# TW3-16_V0_2.net
KiCad netlist of a schematic drawn in Altium Designer
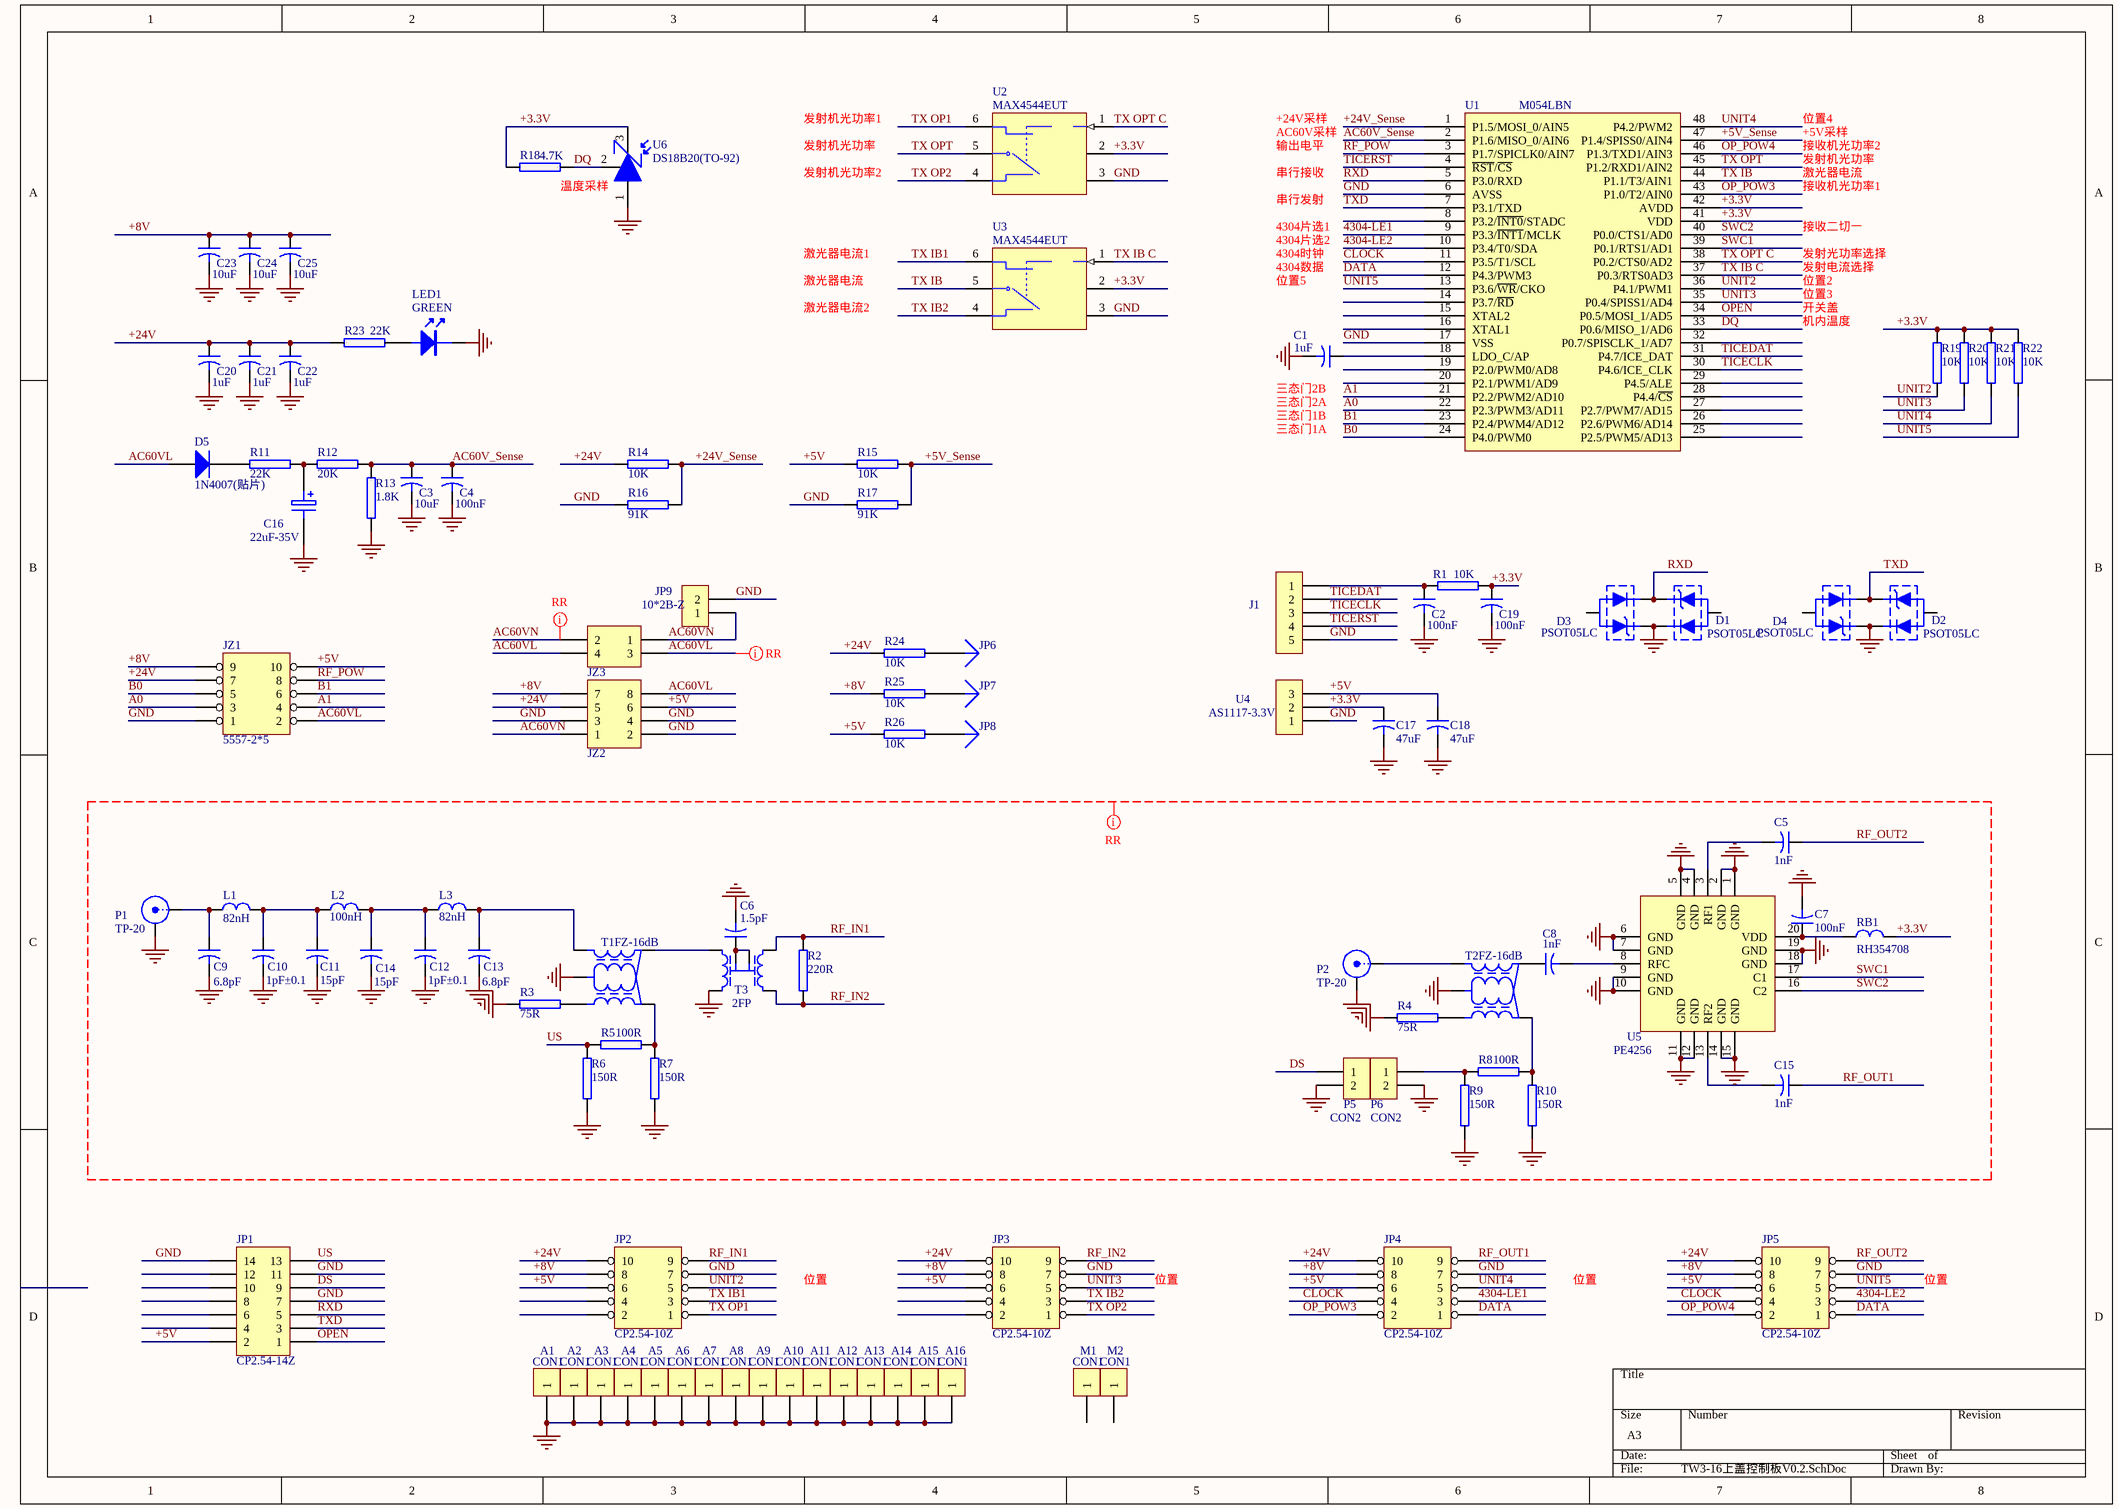
[diagram p0: TW3-16上盖控制板V0.2.SchDoc]

(export (version "E")
  (design (tool "Eeschema 10.0.6"))
  (components
    (comp (ref "A1")
      (value "CON1")
      (footprint "PAD-6mm")
      (description "Connector")
      (libsource (lib "Miscellaneous Devices") (part "CON1"))
    )
    (comp (ref "A2")
      (value "CON1")
      (footprint "PAD-6mm")
      (description "Connector")
      (libsource (lib "Miscellaneous Devices") (part "CON1"))
    )
    (comp (ref "A3")
      (value "CON1")
      (footprint "PAD-6mm")
      (description "Connector")
      (libsource (lib "Miscellaneous Devices") (part "CON1"))
    )
    (comp (ref "A4")
      (value "CON1")
      (footprint "PAD-6mm")
      (description "Connector")
      (libsource (lib "Miscellaneous Devices") (part "CON1"))
    )
    (comp (ref "A5")
      (value "CON1")
      (footprint "PAD-6mm")
      (description "Connector")
      (libsource (lib "Miscellaneous Devices") (part "CON1"))
    )
    (comp (ref "A6")
      (value "CON1")
      (footprint "PAD-6mm")
      (description "Connector")
      (libsource (lib "Miscellaneous Devices") (part "CON1"))
    )
    (comp (ref "A7")
      (value "CON1")
      (footprint "PAD-6mm")
      (description "Connector")
      (libsource (lib "Miscellaneous Devices") (part "CON1"))
    )
    (comp (ref "A8")
      (value "CON1")
      (footprint "PAD-6mm")
      (description "Connector")
      (libsource (lib "Miscellaneous Devices") (part "CON1"))
    )
    (comp (ref "A9")
      (value "CON1")
      (footprint "PAD-6mm")
      (description "Connector")
      (libsource (lib "Miscellaneous Devices") (part "CON1"))
    )
    (comp (ref "A10")
      (value "CON1")
      (footprint "PAD-6mm")
      (description "Connector")
      (libsource (lib "Miscellaneous Devices") (part "CON1"))
    )
    (comp (ref "A11")
      (value "CON1")
      (footprint "PAD-6mm")
      (description "Connector")
      (libsource (lib "Miscellaneous Devices") (part "CON1"))
    )
    (comp (ref "A12")
      (value "CON1")
      (footprint "PAD-6mm")
      (description "Connector")
      (libsource (lib "Miscellaneous Devices") (part "CON1"))
    )
    (comp (ref "A13")
      (value "CON1")
      (footprint "PAD-6mm")
      (description "Connector")
      (libsource (lib "Miscellaneous Devices") (part "CON1"))
    )
    (comp (ref "A14")
      (value "CON1")
      (footprint "PAD-6mm")
      (description "Connector")
      (libsource (lib "Miscellaneous Devices") (part "CON1"))
    )
    (comp (ref "A15")
      (value "CON1")
      (footprint "PAD-6mm")
      (description "Connector")
      (libsource (lib "Miscellaneous Devices") (part "CON1"))
    )
    (comp (ref "A16")
      (value "CON1")
      (footprint "PAD-6mm")
      (description "Connector")
      (libsource (lib "Miscellaneous Devices") (part "CON1"))
    )
    (comp (ref "C1")
      (value "1uF")
      (footprint "0603")
      (description "贴片电容")
      (fields (field (name "Comment") "CT41-0603-B1uF-25V-K"))
      (libsource (lib "Miscellaneous Devices") (part "Cap2"))
    )
    (comp (ref "C2")
      (value "100nF")
      (footprint "0603")
      (description "贴片电容")
      (fields (field (name "Comment") "CT41-0603-B100nF-50V-K"))
      (libsource (lib "Miscellaneous Devices") (part "Cap2"))
    )
    (comp (ref "C3")
      (value "10uF")
      (footprint "1206")
      (description "贴片电容")
      (fields (field (name "Comment") "16V-10uF±10%-X7R-1206"))
      (libsource (lib "Miscellaneous Devices") (part "Cap2"))
    )
    (comp (ref "C4")
      (value "100nF")
      (footprint "0603")
      (description "贴片电容")
      (fields (field (name "Comment") "CT41-0603-B100nF-50V-K"))
      (libsource (lib "Miscellaneous Devices") (part "Cap2"))
    )
    (comp (ref "C5")
      (value "1nF")
      (footprint "0603")
      (description "贴片电容")
      (fields (field (name "Comment") "CT41-0603-B1nF-50V-J"))
      (libsource (lib "Miscellaneous Devices") (part "Cap2"))
    )
    (comp (ref "C6")
      (value "1.5pF")
      (footprint "0603")
      (description "贴片电容")
      (fields (field (name "Comment") "CC41-0603-CG1.5pF-50V-C"))
      (libsource (lib "Miscellaneous Devices") (part "Cap2"))
    )
    (comp (ref "C7")
      (value "100nF")
      (footprint "0603")
      (description "贴片电容")
      (fields (field (name "Comment") "CT41-0603-B100nF-50V-K"))
      (libsource (lib "Miscellaneous Devices") (part "Cap2"))
    )
    (comp (ref "C8")
      (value "1nF")
      (footprint "0603")
      (description "贴片电容")
      (fields (field (name "Comment") "CT41-0603-B1nF-50V-J"))
      (libsource (lib "Miscellaneous Devices") (part "Cap2"))
    )
    (comp (ref "C9")
      (value "6.8pF")
      (footprint "0603")
      (description "贴片电容")
      (fields (field (name "Comment") "CC41-0603-CG6.8pF-50V-C"))
      (libsource (lib "Miscellaneous Devices") (part "Cap2"))
    )
    (comp (ref "C10")
      (value "1pF±0.1")
      (footprint "0603")
      (description "贴片电容")
      (fields (field (name "Comment") "CC41-0603-CG1pF-50V-B"))
      (libsource (lib "Miscellaneous Devices") (part "Cap2"))
    )
    (comp (ref "C11")
      (value "15pF")
      (footprint "0603")
      (description "贴片电容")
      (fields (field (name "Comment") "CC41-0603-CG15pF-50V-J"))
      (libsource (lib "Miscellaneous Devices") (part "Cap2"))
    )
    (comp (ref "C12")
      (value "1pF±0.1")
      (footprint "0603")
      (description "贴片电容")
      (fields (field (name "Comment") "CC41-0603-CG1pF-50V-B"))
      (libsource (lib "Miscellaneous Devices") (part "Cap2"))
    )
    (comp (ref "C13")
      (value "6.8pF")
      (footprint "0603")
      (description "贴片电容")
      (fields (field (name "Comment") "CC41-0603-CG6.8pF-50V-C"))
      (libsource (lib "Miscellaneous Devices") (part "Cap2"))
    )
    (comp (ref "C14")
      (value "15pF")
      (footprint "0603")
      (description "贴片电容")
      (fields (field (name "Comment") "CC41-0603-CG15pF-50V-J"))
      (libsource (lib "Miscellaneous Devices") (part "Cap2"))
    )
    (comp (ref "C15")
      (value "1nF")
      (footprint "0603")
      (description "贴片电容")
      (fields (field (name "Comment") "CT41-0603-B1nF-50V-J"))
      (libsource (lib "Miscellaneous Devices") (part "Cap2"))
    )
    (comp (ref "C16")
      (value "22uF-35V")
      (footprint "RB-SMT-6.3X5.4")
      (description "贴片铝电解电容")
      (fields (field (name "Comment") "SCD11-6.3*5.4-22uF-35V-K"))
      (libsource (lib "Miscellaneous Devices") (part "ELECTRO1"))
    )
    (comp (ref "C17")
      (value "47uF")
      (footprint "1206")
      (description "贴片电容")
      (fields (field (name "Comment") "CT41-1206-F476-10V-M"))
      (libsource (lib "Miscellaneous Devices") (part "Cap2"))
    )
    (comp (ref "C18")
      (value "47uF")
      (footprint "1206")
      (description "贴片电容")
      (fields (field (name "Comment") "CT41-1206-F476-10V-M"))
      (libsource (lib "Miscellaneous Devices") (part "Cap2"))
    )
    (comp (ref "C19")
      (value "100nF")
      (footprint "0603")
      (description "贴片电容")
      (fields (field (name "Comment") "CT41-0603-B100nF-50V-K"))
      (libsource (lib "Miscellaneous Devices") (part "Cap2"))
    )
    (comp (ref "C20")
      (value "1uF")
      (footprint "1206")
      (description "贴片电容")
      (fields (field (name "Comment") "CT41-1206-B1uF-50V-K"))
      (libsource (lib "Miscellaneous Devices") (part "Cap2"))
    )
    (comp (ref "C21")
      (value "1uF")
      (footprint "1206")
      (description "贴片电容")
      (fields (field (name "Comment") "CT41-1206-B1uF-50V-K"))
      (libsource (lib "Miscellaneous Devices") (part "Cap2"))
    )
    (comp (ref "C22")
      (value "1uF")
      (footprint "1206")
      (description "贴片电容")
      (fields (field (name "Comment") "CT41-1206-B1uF-50V-K"))
      (libsource (lib "Miscellaneous Devices") (part "Cap2"))
    )
    (comp (ref "C23")
      (value "10uF")
      (footprint "1206")
      (description "贴片电容")
      (fields (field (name "Comment") "16V-10uF±10%-X7R-1206"))
      (libsource (lib "Miscellaneous Devices") (part "Cap2"))
    )
    (comp (ref "C24")
      (value "10uF")
      (footprint "1206")
      (description "贴片电容")
      (fields (field (name "Comment") "16V-10uF±10%-X7R-1206"))
      (libsource (lib "Miscellaneous Devices") (part "Cap2"))
    )
    (comp (ref "C25")
      (value "10uF")
      (footprint "1206")
      (description "贴片电容")
      (fields (field (name "Comment") "16V-10uF±10%-X7R-1206"))
      (libsource (lib "Miscellaneous Devices") (part "Cap2"))
    )
    (comp (ref "D1")
      (value "PSOT05LC")
      (footprint "SOT-23")
      (fields (field (name "Comment") "集成块"))
      (libsource (lib "*") (part "PSOT05LC"))
    )
    (comp (ref "D2")
      (value "PSOT05LC")
      (footprint "SOT-23")
      (fields (field (name "Comment") "集成块"))
      (libsource (lib "*") (part "PSOT05LC"))
    )
    (comp (ref "D3")
      (value "PSOT05LC")
      (footprint "SOT-23")
      (fields (field (name "Comment") "集成块"))
      (libsource (lib "*") (part "PSOT05LC"))
    )
    (comp (ref "D4")
      (value "PSOT05LC")
      (footprint "SOT-23")
      (fields (field (name "Comment") "集成块"))
      (libsource (lib "*") (part "PSOT05LC"))
    )
    (comp (ref "D5")
      (value "1N4007(贴片)")
      (footprint "DO-SMA")
      (description "贴片二极管")
      (libsource (lib "Miscellaneous Devices") (part "Diode 1N4007"))
    )
    (comp (ref "J1")
      (value "IDC单排插针")
      (footprint "SIP5")
      (description "1×5（2.54mm）")
      (libsource (lib "*") (part "CON5"))
    )
    (comp (ref "JP1")
      (value "CP2.54-14Z-S-K(排母)")
      (footprint "IDC-14Z")
      (description "双排14芯插座")
      (fields (field (name "VALLUE") "CP2.54-14Z"))
      (libsource (lib "Miscellaneous Connectors") (part "Header 7X2"))
    )
    (comp (ref "JP2")
      (value "CP2.54-10Z")
      (footprint "IDC-10Z")
      (description "双排10芯插座")
      (fields (field (name "Comment") "CP2.54-10Z-S-K(排母)"))
      (libsource (lib "Miscellaneous Devices") (part "HEADER 5X2"))
    )
    (comp (ref "JP3")
      (value "CP2.54-10Z")
      (footprint "IDC-10Z")
      (description "双排10芯插座")
      (fields (field (name "Comment") "CP2.54-10Z-S-K(排母)"))
      (libsource (lib "Miscellaneous Devices") (part "HEADER 5X2"))
    )
    (comp (ref "JP4")
      (value "CP2.54-10Z")
      (footprint "IDC-10Z")
      (description "双排10芯插座")
      (fields (field (name "Comment") "CP2.54-10Z-S-K(排母)"))
      (libsource (lib "Miscellaneous Devices") (part "HEADER 5X2"))
    )
    (comp (ref "JP5")
      (value "CP2.54-10Z")
      (footprint "IDC-10Z")
      (description "双排10芯插座")
      (fields (field (name "Comment") "CP2.54-10Z-S-K(排母)"))
      (libsource (lib "Miscellaneous Devices") (part "HEADER 5X2"))
    )
    (comp (ref "JP6")
      (value "CK-1A")
      (footprint "TEST1")
      (description "测试柱")
      (libsource (lib "Miscellaneous Connectors") (part "Plug"))
    )
    (comp (ref "JP7")
      (value "CK-1A")
      (footprint "TEST1")
      (description "测试柱")
      (libsource (lib "Miscellaneous Connectors") (part "Plug"))
    )
    (comp (ref "JP8")
      (value "CK-1A")
      (footprint "TEST1")
      (description "测试柱")
      (libsource (lib "Miscellaneous Connectors") (part "Plug"))
    )
    (comp (ref "JP9")
      (value "10*2B-Z")
      (footprint "AC-10mm")
      (description "二芯针座")
      (libsource (lib "") (part "CON2_1"))
    )
    (comp (ref "JZ1")
      (value "5557-2*5")
      (footprint "5557-2*5")
      (description "十芯插座")
      (libsource (lib "") (part "HEADER 5X2_1"))
    )
    (comp (ref "JZ2")
      (value "5557-8A")
      (footprint "5557-2X4")
      (description "八芯插座")
      (libsource (lib "Miscellaneous Connectors") (part "Header 4X2H"))
    )
    (comp (ref "JZ3")
      (value "5557-2*2座")
      (footprint "5557-2X2")
      (description "4芯插座")
      (libsource (lib "Miscellaneous Connectors") (part "Header 2X2H"))
    )
    (comp (ref "L1")
      (value "82nH")
      (footprint "0805")
      (description "陶瓷线绕电感")
      (fields (field (name "Comment") "HDW0805UC082JGT"))
      (libsource (lib "SCH") (part "L3"))
    )
    (comp (ref "L2")
      (value "100nH")
      (footprint "0805")
      (description "陶瓷线绕电感")
      (fields (field (name "Comment") "HDW0805UCR10JGT"))
      (libsource (lib "SCH") (part "L3"))
    )
    (comp (ref "L3")
      (value "82nH")
      (footprint "0805")
      (description "陶瓷线绕电感")
      (fields (field (name "Comment") "HDW1008UC082JGT"))
      (libsource (lib "SCH") (part "L3"))
    )
    (comp (ref "LED1")
      (value "GREEN")
      (footprint "1206-D")
      (description "发光二极管")
      (fields (field (name "Comment") "LED-1206-G(SMD)"))
      (libsource (lib "SCH") (part "LED-1"))
    )
    (comp (ref "M1")
      (value "CON1")
      (footprint "MArK-1")
      (description "Connector")
      (libsource (lib "Miscellaneous Devices") (part "CON1"))
    )
    (comp (ref "M2")
      (value "CON1")
      (footprint "MArK-1")
      (description "Connector")
      (libsource (lib "Miscellaneous Devices") (part "CON1"))
    )
    (comp (ref "P1")
      (value "TP-20")
      (footprint "PAD-DLJT2")
      (description "测试插孔")
      (fields (field (name "Comment") "02TV阳座"))
      (libsource (lib "Miscellaneous Connectors") (part "SMB"))
    )
    (comp (ref "P2")
      (value "TP-20")
      (footprint "PAD-DLJT2")
      (description "测试插孔")
      (fields (field (name "Comment") "02TV阳座"))
      (libsource (lib "Miscellaneous Connectors") (part "SMB"))
    )
    (comp (ref "P5")
      (value "CON2")
      (footprint "PAD-DLJT2")
      (description "Connector")
      (libsource (lib "") (part "CON2_2"))
    )
    (comp (ref "P6")
      (value "CON2")
      (footprint "PAD-DLJT2")
      (description "Connector")
      (libsource (lib "Miscellaneous Devices") (part "CON2"))
    )
    (comp (ref "R1")
      (value "10K")
      (footprint "0603")
      (description "贴片电阻")
      (fields (field (name "Comment") "SRI11-0603-10KΩ-J"))
      (libsource (lib "") (part "RES1_3"))
    )
    (comp (ref "R2")
      (value "220R")
      (footprint "0603")
      (description "贴片电阻")
      (fields (field (name "Comment") "SRI11-0603-220Ω-J"))
      (libsource (lib "*") (part "RES1"))
    )
    (comp (ref "R3")
      (value "75R")
      (footprint "0603")
      (description "贴片电阻")
      (fields (field (name "Comment") "SRI11-0603-75Ω-J"))
      (libsource (lib "") (part "RES1_1"))
    )
    (comp (ref "R4")
      (value "75R")
      (footprint "0603")
      (description "贴片电阻")
      (fields (field (name "Comment") "SRI11-0603-75Ω-J"))
      (libsource (lib "") (part "RES1_1"))
    )
    (comp (ref "R5")
      (value "100R")
      (footprint "0603")
      (description "贴片电阻")
      (fields (field (name "Comment") "SRI11-0603-100Ω-J"))
      (libsource (lib "") (part "RES1_1"))
    )
    (comp (ref "R6")
      (value "150R")
      (footprint "0603")
      (description "贴片电阻")
      (fields (field (name "Comment") "SRI11-0603-150Ω-J"))
      (libsource (lib "") (part "RES1_2"))
    )
    (comp (ref "R7")
      (value "150R")
      (footprint "0603")
      (description "贴片电阻")
      (fields (field (name "Comment") "SRI11-0603-150Ω-J"))
      (libsource (lib "") (part "RES1_2"))
    )
    (comp (ref "R8")
      (value "100R")
      (footprint "0603")
      (description "贴片电阻")
      (fields (field (name "Comment") "SRI11-0603-100Ω-J"))
      (libsource (lib "") (part "RES1_1"))
    )
    (comp (ref "R9")
      (value "150R")
      (footprint "0603")
      (description "贴片电阻")
      (fields (field (name "Comment") "SRI11-0603-150Ω-J"))
      (libsource (lib "") (part "RES1_2"))
    )
    (comp (ref "R10")
      (value "150R")
      (footprint "0603")
      (description "贴片电阻")
      (fields (field (name "Comment") "SRI11-0603-150Ω-J"))
      (libsource (lib "") (part "RES1_2"))
    )
    (comp (ref "R11")
      (value "22K")
      (footprint "0805")
      (description "贴片电阻")
      (fields (field (name "Comment") "SRI11-0805-22KΩ-J"))
      (libsource (lib "*") (part "RES1"))
    )
    (comp (ref "R12")
      (value "20K")
      (footprint "0805")
      (description "贴片电阻")
      (fields (field (name "Comment") "SRI11-0805-20KΩ-J"))
      (libsource (lib "*") (part "RES1"))
    )
    (comp (ref "R13")
      (value "1.8K")
      (footprint "0805")
      (description "贴片电阻")
      (fields (field (name "Comment") "SRI11-0805-1.8KΩ-J"))
      (libsource (lib "") (part "RES1_4"))
    )
    (comp (ref "R14")
      (value "10K")
      (footprint "0603")
      (description "贴片电阻")
      (fields (field (name "Comment") "SRI11-0603-10KΩ-J"))
      (libsource (lib "") (part "RES1_1"))
    )
    (comp (ref "R15")
      (value "10K")
      (footprint "0603")
      (description "贴片电阻")
      (fields (field (name "Comment") "SRI11-0603-10KΩ-J"))
      (libsource (lib "") (part "RES1_1"))
    )
    (comp (ref "R16")
      (value "91K")
      (footprint "0603")
      (description "贴片电阻")
      (fields (field (name "Comment") "SRI11-0603-91KΩ-J"))
      (libsource (lib "") (part "RES1_1"))
    )
    (comp (ref "R17")
      (value "91K")
      (footprint "0603")
      (description "贴片电阻")
      (fields (field (name "Comment") "SRI11-0603-91KΩ-J"))
      (libsource (lib "") (part "RES1_1"))
    )
    (comp (ref "R18")
      (value "4.7K")
      (footprint "0603")
      (description "贴片电阻")
      (fields (field (name "Comment") "SRI11-0603-4.7KΩ-J"))
      (libsource (lib "") (part "RES1_2"))
    )
    (comp (ref "R19")
      (value "10K")
      (footprint "0603")
      (description "贴片电阻")
      (fields (field (name "Comment") "SRI11-0603-10KΩ-J"))
      (libsource (lib "") (part "RES1_1"))
    )
    (comp (ref "R20")
      (value "10K")
      (footprint "0603")
      (description "贴片电阻")
      (fields (field (name "Comment") "SRI11-0603-10KΩ-J"))
      (libsource (lib "") (part "RES1_1"))
    )
    (comp (ref "R21")
      (value "10K")
      (footprint "0603")
      (description "贴片电阻")
      (fields (field (name "Comment") "SRI11-0603-10KΩ-J"))
      (libsource (lib "") (part "RES1_1"))
    )
    (comp (ref "R22")
      (value "10K")
      (footprint "0603")
      (description "贴片电阻")
      (fields (field (name "Comment") "SRI11-0603-10KΩ-J"))
      (libsource (lib "") (part "RES1_1"))
    )
    (comp (ref "R23")
      (value "22K")
      (footprint "0603")
      (description "贴片电阻")
      (fields (field (name "Comment") "SRI11-0603-22KΩ-J"))
      (libsource (lib "*") (part "RESSMD_0603"))
    )
    (comp (ref "R24")
      (value "10K")
      (footprint "0603")
      (description "贴片电阻")
      (fields (field (name "Comment") "SRI11-0603-10KΩ-J"))
      (libsource (lib "") (part "RES1_1"))
    )
    (comp (ref "R25")
      (value "10K")
      (footprint "0603")
      (description "贴片电阻")
      (fields (field (name "Comment") "SRI11-0603-10KΩ-J"))
      (libsource (lib "") (part "RES1_1"))
    )
    (comp (ref "R26")
      (value "10K")
      (footprint "0603")
      (description "贴片电阻")
      (fields (field (name "Comment") "SRI11-0603-10KΩ-J"))
      (libsource (lib "") (part "RES1_1"))
    )
    (comp (ref "RB1")
      (value "RH354708")
      (footprint "L12MM")
      (description "插件磁珠")
      (libsource (lib "SCH") (part "L3"))
    )
    (comp (ref "T1")
      (value "FZ-16dB")
      (footprint "T-SM16")
      (description "高频变压器")
      (fields (field (name "Comment") "F06401C"))
      (libsource (lib "SCH") (part "FZ"))
    )
    (comp (ref "T2")
      (value "FZ-16dB")
      (footprint "T-SM16")
      (description "高频变压器")
      (fields (field (name "Comment") "F06401C"))
      (libsource (lib "SCH") (part "FZ"))
    )
    (comp (ref "T3")
      (value "2FP")
      (footprint "STB-RG33")
      (description "高频变压器")
      (fields (field (name "Comment") "F06502S"))
      (libsource (lib "*") (part "FP"))
    )
    (comp (ref "U1")
      (value "M054LBN")
      (footprint "LQFP-48")
      (description "集成块")
      (libsource (lib "*") (part "M052LBN"))
    )
    (comp (ref "U2")
      (value "MAX4544EUT")
      (footprint "SOT23-6")
      (fields (field (name "Comment") "集成块"))
      (libsource (lib "*") (part "MAX4544EUT-T"))
    )
    (comp (ref "U3")
      (value "MAX4544EUT")
      (footprint "SOT23-6")
      (fields (field (name "Comment") "集成块"))
      (libsource (lib "*") (part "MAX4544EUT-T"))
    )
    (comp (ref "U4")
      (value "AS1117-3.3V")
      (footprint "SOT-223-3L")
      (description "集成块")
      (libsource (lib "Miscellaneous Devices") (part "CON3"))
    )
    (comp (ref "U5")
      (value "PE4256")
      (footprint "QFN-20")
      (description "集成块")
      (fields (field (name "Comment") "PE4256DS"))
      (libsource (lib "*") (part "PE4256"))
    )
    (comp (ref "U6")
      (value "DS18B20(TO-92)")
      (footprint "TO-92-78L")
      (description "集成块")
      (libsource (lib "*") (part "DS18B20"))
    )
  )
  (nets
    (net (code "1") (name "/+3.3V") (class "Default")
      (node (ref "C17") (pin "1") (pinfunction "1_1") (pintype "passive"))
      (node (ref "C19") (pin "1") (pinfunction "1_1") (pintype "passive"))
      (node (ref "R1") (pin "2") (pinfunction "2_2") (pintype "passive"))
      (node (ref "R18") (pin "2") (pinfunction "2_2") (pintype "passive"))
      (node (ref "R19") (pin "1") (pinfunction "1_1") (pintype "passive"))
      (node (ref "R20") (pin "1") (pinfunction "1_1") (pintype "passive"))
      (node (ref "R21") (pin "1") (pinfunction "1_1") (pintype "passive"))
      (node (ref "R22") (pin "1") (pinfunction "1_1") (pintype "passive"))
      (node (ref "RB1") (pin "2") (pinfunction "2_2") (pintype "passive"))
      (node (ref "U1") (pin "41") (pinfunction "VDD_41") (pintype "passive"))
      (node (ref "U1") (pin "42") (pinfunction "AVDD_42") (pintype "passive"))
      (node (ref "U2") (pin "2") (pinfunction "V+_2") (pintype "passive"))
      (node (ref "U3") (pin "2") (pinfunction "V+_2") (pintype "passive"))
      (node (ref "U4") (pin "2") (pinfunction "2_2") (pintype "passive"))
      (node (ref "U6") (pin "3") (pinfunction "Vdd_3") (pintype "passive"))
    )
    (net (code "2") (name "/+5V") (class "Default")
      (node (ref "C18") (pin "1") (pinfunction "1_1") (pintype "passive"))
      (node (ref "JP1") (pin "2") (pinfunction "2_2") (pintype "passive"))
      (node (ref "JP2") (pin "6") (pinfunction "6_6") (pintype "passive"))
      (node (ref "JP3") (pin "6") (pinfunction "6_6") (pintype "passive"))
      (node (ref "JP4") (pin "6") (pinfunction "6_6") (pintype "passive"))
      (node (ref "JP5") (pin "6") (pinfunction "6_6") (pintype "passive"))
      (node (ref "JZ1") (pin "10") (pinfunction "10_10") (pintype "passive"))
      (node (ref "JZ2") (pin "6") (pinfunction "6_6") (pintype "passive"))
      (node (ref "R15") (pin "2") (pinfunction "2_2") (pintype "passive"))
      (node (ref "R26") (pin "2") (pinfunction "2_2") (pintype "passive"))
      (node (ref "U4") (pin "3") (pinfunction "3_3") (pintype "passive"))
    )
    (net (code "3") (name "/+5V_Sense") (class "Default")
      (node (ref "R15") (pin "1") (pinfunction "1_1") (pintype "passive"))
      (node (ref "R17") (pin "1") (pinfunction "1_1") (pintype "passive"))
      (node (ref "U1") (pin "47") (pinfunction "P1.4/SPISS0/AIN4_47") (pintype "passive"))
    )
    (net (code "4") (name "/+8V") (class "Default")
      (node (ref "C23") (pin "1") (pinfunction "1_1") (pintype "passive"))
      (node (ref "C24") (pin "1") (pinfunction "1_1") (pintype "passive"))
      (node (ref "C25") (pin "1") (pinfunction "1_1") (pintype "passive"))
      (node (ref "JP2") (pin "8") (pinfunction "8_8") (pintype "passive"))
      (node (ref "JP3") (pin "8") (pinfunction "8_8") (pintype "passive"))
      (node (ref "JP4") (pin "8") (pinfunction "8_8") (pintype "passive"))
      (node (ref "JP5") (pin "8") (pinfunction "8_8") (pintype "passive"))
      (node (ref "JZ1") (pin "9") (pinfunction "9_9") (pintype "passive"))
      (node (ref "JZ2") (pin "7") (pinfunction "7_7") (pintype "passive"))
      (node (ref "R25") (pin "2") (pinfunction "2_2") (pintype "passive"))
    )
    (net (code "5") (name "/+24V") (class "Default")
      (node (ref "C20") (pin "1") (pinfunction "1_1") (pintype "passive"))
      (node (ref "C21") (pin "1") (pinfunction "1_1") (pintype "passive"))
      (node (ref "C22") (pin "1") (pinfunction "1_1") (pintype "passive"))
      (node (ref "JP2") (pin "10") (pinfunction "10_10") (pintype "passive"))
      (node (ref "JP3") (pin "10") (pinfunction "10_10") (pintype "passive"))
      (node (ref "JP4") (pin "10") (pinfunction "10_10") (pintype "passive"))
      (node (ref "JP5") (pin "10") (pinfunction "10_10") (pintype "passive"))
      (node (ref "JZ1") (pin "7") (pinfunction "7_7") (pintype "passive"))
      (node (ref "JZ2") (pin "5") (pinfunction "5_5") (pintype "passive"))
      (node (ref "R14") (pin "2") (pinfunction "2_2") (pintype "passive"))
      (node (ref "R23") (pin "1") (pinfunction "1_1") (pintype "passive"))
      (node (ref "R24") (pin "2") (pinfunction "2_2") (pintype "passive"))
    )
    (net (code "6") (name "/+24V_Sense") (class "Default")
      (node (ref "R14") (pin "1") (pinfunction "1_1") (pintype "passive"))
      (node (ref "R16") (pin "1") (pinfunction "1_1") (pintype "passive"))
      (node (ref "U1") (pin "1") (pinfunction "P1.5/MOSI_0/AIN5_1") (pintype "passive"))
    )
    (net (code "7") (name "/4304-LE1") (class "Default")
      (node (ref "JP4") (pin "3") (pinfunction "3_3") (pintype "passive"))
      (node (ref "U1") (pin "9") (pinfunction "P3.3/~{INT1}/MCLK_9") (pintype "passive"))
    )
    (net (code "8") (name "/4304-LE2") (class "Default")
      (node (ref "JP5") (pin "3") (pinfunction "3_3") (pintype "passive"))
      (node (ref "U1") (pin "10") (pinfunction "P3.4/T0/SDA_10") (pintype "passive"))
    )
    (net (code "9") (name "/A0") (class "Default")
      (node (ref "JZ1") (pin "3") (pinfunction "3_3") (pintype "passive"))
      (node (ref "U1") (pin "22") (pinfunction "P2.3/PWM3/AD11_22") (pintype "passive"))
    )
    (net (code "10") (name "/A1") (class "Default")
      (node (ref "JZ1") (pin "4") (pinfunction "4_4") (pintype "passive"))
      (node (ref "U1") (pin "21") (pinfunction "P2.2/PWM2/AD10_21") (pintype "passive"))
    )
    (net (code "11") (name "/AC60VL") (class "Default")
      (node (ref "D5") (pin "1") (pinfunction "A_1") (pintype "passive"))
      (node (ref "JZ1") (pin "2") (pinfunction "2_2") (pintype "passive"))
      (node (ref "JZ2") (pin "8") (pinfunction "8_8") (pintype "passive"))
      (node (ref "JZ3") (pin "3") (pinfunction "3_3") (pintype "passive"))
      (node (ref "JZ3") (pin "4") (pinfunction "4_4") (pintype "passive"))
    )
    (net (code "12") (name "/AC60VN") (class "Default")
      (node (ref "JP9") (pin "1") (pinfunction "1_1") (pintype "passive"))
      (node (ref "JZ2") (pin "1") (pinfunction "1_1") (pintype "passive"))
      (node (ref "JZ3") (pin "1") (pinfunction "1_1") (pintype "passive"))
      (node (ref "JZ3") (pin "2") (pinfunction "2_2") (pintype "passive"))
    )
    (net (code "13") (name "/AC60V_Sense") (class "Default")
      (node (ref "C3") (pin "1") (pinfunction "1_1") (pintype "passive"))
      (node (ref "C4") (pin "1") (pinfunction "1_1") (pintype "passive"))
      (node (ref "R12") (pin "2") (pinfunction "2_2") (pintype "passive"))
      (node (ref "R13") (pin "1") (pinfunction "1_1") (pintype "passive"))
      (node (ref "U1") (pin "2") (pinfunction "P1.6/MISO_0/AIN6_2") (pintype "passive"))
    )
    (net (code "14") (name "/B0") (class "Default")
      (node (ref "JZ1") (pin "5") (pinfunction "5_5") (pintype "passive"))
      (node (ref "U1") (pin "24") (pinfunction "P4.0/PWM0_24") (pintype "passive"))
    )
    (net (code "15") (name "/B1") (class "Default")
      (node (ref "JZ1") (pin "6") (pinfunction "6_6") (pintype "passive"))
      (node (ref "U1") (pin "23") (pinfunction "P2.4/PWM4/AD12_23") (pintype "passive"))
    )
    (net (code "16") (name "/CLOCK") (class "Default")
      (node (ref "JP4") (pin "4") (pinfunction "4_4") (pintype "passive"))
      (node (ref "JP5") (pin "4") (pinfunction "4_4") (pintype "passive"))
      (node (ref "U1") (pin "11") (pinfunction "P3.5/T1/SCL_11") (pintype "passive"))
    )
    (net (code "17") (name "/DATA") (class "Default")
      (node (ref "JP4") (pin "1") (pinfunction "1_1") (pintype "passive"))
      (node (ref "JP5") (pin "1") (pinfunction "1_1") (pintype "passive"))
      (node (ref "U1") (pin "12") (pinfunction "P4.3/PWM3_12") (pintype "passive"))
    )
    (net (code "18") (name "/DQ") (class "Default")
      (node (ref "R18") (pin "1") (pinfunction "1_1") (pintype "passive"))
      (node (ref "U1") (pin "33") (pinfunction "P0.6/MISO_1/AD6_33") (pintype "passive"))
      (node (ref "U6") (pin "2") (pinfunction "DQ_2") (pintype "passive"))
    )
    (net (code "19") (name "/DS") (class "Default")
      (node (ref "JP1") (pin "9") (pinfunction "9_9") (pintype "passive"))
      (node (ref "P5") (pin "1") (pinfunction "1_1") (pintype "passive"))
    )
    (net (code "20") (name "/OPEN") (class "Default")
      (node (ref "JP1") (pin "1") (pinfunction "1_1") (pintype "passive"))
      (node (ref "U1") (pin "34") (pinfunction "P0.5/MOSI_1/AD5_34") (pintype "passive"))
    )
    (net (code "21") (name "/OP_POW3") (class "Default")
      (node (ref "JP4") (pin "2") (pinfunction "2_2") (pintype "passive"))
      (node (ref "U1") (pin "43") (pinfunction "P1.0/T2/AIN0_43") (pintype "passive"))
    )
    (net (code "22") (name "/OP_POW4") (class "Default")
      (node (ref "JP5") (pin "2") (pinfunction "2_2") (pintype "passive"))
      (node (ref "U1") (pin "46") (pinfunction "P1.3/TXD1/AIN3_46") (pintype "passive"))
    )
    (net (code "23") (name "/RF_IN1") (class "Default")
      (node (ref "JP2") (pin "9") (pinfunction "9_9") (pintype "passive"))
      (node (ref "R2") (pin "2") (pinfunction "2_2") (pintype "passive"))
      (node (ref "T3") (pin "4") (pinfunction "OUT_4") (pintype "passive"))
    )
    (net (code "24") (name "/RF_IN2") (class "Default")
      (node (ref "JP3") (pin "9") (pinfunction "9_9") (pintype "passive"))
      (node (ref "R2") (pin "1") (pinfunction "1_1") (pintype "passive"))
      (node (ref "T3") (pin "3") (pinfunction "OUT_3") (pintype "passive"))
    )
    (net (code "25") (name "/RF_OUT1") (class "Default")
      (node (ref "C15") (pin "1") (pinfunction "1_1") (pintype "passive"))
      (node (ref "JP4") (pin "9") (pinfunction "9_9") (pintype "passive"))
    )
    (net (code "26") (name "/RF_OUT2") (class "Default")
      (node (ref "C5") (pin "1") (pinfunction "1_1") (pintype "passive"))
      (node (ref "JP5") (pin "9") (pinfunction "9_9") (pintype "passive"))
    )
    (net (code "27") (name "/RF_POW") (class "Default")
      (node (ref "JZ1") (pin "8") (pinfunction "8_8") (pintype "passive"))
      (node (ref "U1") (pin "3") (pinfunction "P1.7/SPICLK0/AIN7_3") (pintype "passive"))
    )
    (net (code "28") (name "/RXD") (class "Default")
      (node (ref "D1") (pin "1") (pinfunction "1_1") (pintype "passive"))
      (node (ref "D3") (pin "2") (pinfunction "2_2") (pintype "passive"))
      (node (ref "JP1") (pin "5") (pinfunction "5_5") (pintype "passive"))
      (node (ref "U1") (pin "5") (pinfunction "P3.0/RXD_5") (pintype "passive"))
    )
    (net (code "29") (name "/SWC1") (class "Default")
      (node (ref "U1") (pin "39") (pinfunction "P0.1/RTS1/AD1_39") (pintype "passive"))
      (node (ref "U5") (pin "17") (pinfunction "C1_17") (pintype "passive"))
    )
    (net (code "30") (name "/SWC2") (class "Default")
      (node (ref "U1") (pin "40") (pinfunction "P0.0/CTS1/AD0_40") (pintype "passive"))
      (node (ref "U5") (pin "16") (pinfunction "C2_16") (pintype "passive"))
    )
    (net (code "31") (name "/TICECLK") (class "Default")
      (node (ref "J1") (pin "3") (pinfunction "3_3") (pintype "passive"))
      (node (ref "U1") (pin "30") (pinfunction "P4.6/ICE_CLK_30") (pintype "passive"))
    )
    (net (code "32") (name "/TICEDAT") (class "Default")
      (node (ref "J1") (pin "2") (pinfunction "2_2") (pintype "passive"))
      (node (ref "U1") (pin "31") (pinfunction "P4.7/ICE_DAT_31") (pintype "passive"))
    )
    (net (code "33") (name "/TICERST") (class "Default")
      (node (ref "J1") (pin "4") (pinfunction "4_4") (pintype "passive"))
      (node (ref "U1") (pin "4") (pinfunction "~{RST}/~{CS}_4") (pintype "passive"))
    )
    (net (code "34") (name "/TX IB") (class "Default")
      (node (ref "U1") (pin "44") (pinfunction "P1.1/T3/AIN1_44") (pintype "passive"))
      (node (ref "U3") (pin "5") (pinfunction "COM_5") (pintype "passive"))
    )
    (net (code "35") (name "/TX IB C") (class "Default")
      (node (ref "U1") (pin "37") (pinfunction "P0.3/RTS0AD3_37") (pintype "passive"))
      (node (ref "U3") (pin "1") (pinfunction "IN_1") (pintype "input"))
    )
    (net (code "36") (name "/TX IB1") (class "Default")
      (node (ref "JP2") (pin "3") (pinfunction "3_3") (pintype "passive"))
      (node (ref "U3") (pin "6") (pinfunction "NO_6") (pintype "power_in"))
    )
    (net (code "37") (name "/TX IB2") (class "Default")
      (node (ref "JP3") (pin "3") (pinfunction "3_3") (pintype "passive"))
      (node (ref "U3") (pin "4") (pinfunction "NC_4") (pintype "passive"))
    )
    (net (code "38") (name "/TX OP1") (class "Default")
      (node (ref "JP2") (pin "1") (pinfunction "1_1") (pintype "passive"))
      (node (ref "U2") (pin "6") (pinfunction "NO_6") (pintype "power_in"))
    )
    (net (code "39") (name "/TX OP2") (class "Default")
      (node (ref "JP3") (pin "1") (pinfunction "1_1") (pintype "passive"))
      (node (ref "U2") (pin "4") (pinfunction "NC_4") (pintype "passive"))
    )
    (net (code "40") (name "/TX OPT") (class "Default")
      (node (ref "U1") (pin "45") (pinfunction "P1.2/RXD1/AIN2_45") (pintype "passive"))
      (node (ref "U2") (pin "5") (pinfunction "COM_5") (pintype "passive"))
    )
    (net (code "41") (name "/TX OPT C") (class "Default")
      (node (ref "U1") (pin "38") (pinfunction "P0.2/CTS0/AD2_38") (pintype "passive"))
      (node (ref "U2") (pin "1") (pinfunction "IN_1") (pintype "input"))
    )
    (net (code "42") (name "/TXD") (class "Default")
      (node (ref "D2") (pin "1") (pinfunction "1_1") (pintype "passive"))
      (node (ref "D4") (pin "2") (pinfunction "2_2") (pintype "passive"))
      (node (ref "JP1") (pin "3") (pinfunction "3_3") (pintype "passive"))
      (node (ref "U1") (pin "7") (pinfunction "P3.1/TXD_7") (pintype "passive"))
    )
    (net (code "43") (name "/UNIT2") (class "Default")
      (node (ref "JP2") (pin "5") (pinfunction "5_5") (pintype "passive"))
      (node (ref "R19") (pin "2") (pinfunction "2_2") (pintype "passive"))
      (node (ref "U1") (pin "36") (pinfunction "P4.1/PWM1_36") (pintype "passive"))
    )
    (net (code "44") (name "/UNIT3") (class "Default")
      (node (ref "JP3") (pin "5") (pinfunction "5_5") (pintype "passive"))
      (node (ref "R20") (pin "2") (pinfunction "2_2") (pintype "passive"))
      (node (ref "U1") (pin "35") (pinfunction "P0.4/SPISS1/AD4_35") (pintype "passive"))
    )
    (net (code "45") (name "/UNIT4") (class "Default")
      (node (ref "JP4") (pin "5") (pinfunction "5_5") (pintype "passive"))
      (node (ref "R21") (pin "2") (pinfunction "2_2") (pintype "passive"))
      (node (ref "U1") (pin "48") (pinfunction "P4.2/PWM2_48") (pintype "passive"))
    )
    (net (code "46") (name "/UNIT5") (class "Default")
      (node (ref "JP5") (pin "5") (pinfunction "5_5") (pintype "passive"))
      (node (ref "R22") (pin "2") (pinfunction "2_2") (pintype "passive"))
      (node (ref "U1") (pin "13") (pinfunction "P3.6/~{WR}/CKO_13") (pintype "passive"))
    )
    (net (code "47") (name "/US") (class "Default")
      (node (ref "JP1") (pin "13") (pinfunction "13_13") (pintype "passive"))
      (node (ref "R5") (pin "2") (pinfunction "2_2") (pintype "passive"))
      (node (ref "R6") (pin "1") (pinfunction "1_1") (pintype "passive"))
    )
    (net (code "48") (name "GND") (class "Default")
      (node (ref "A1") (pin "1") (pinfunction "1_1") (pintype "passive"))
      (node (ref "A10") (pin "1") (pinfunction "1_1") (pintype "passive"))
      (node (ref "A11") (pin "1") (pinfunction "1_1") (pintype "passive"))
      (node (ref "A12") (pin "1") (pinfunction "1_1") (pintype "passive"))
      (node (ref "A13") (pin "1") (pinfunction "1_1") (pintype "passive"))
      (node (ref "A14") (pin "1") (pinfunction "1_1") (pintype "passive"))
      (node (ref "A15") (pin "1") (pinfunction "1_1") (pintype "passive"))
      (node (ref "A16") (pin "1") (pinfunction "1_1") (pintype "passive"))
      (node (ref "A2") (pin "1") (pinfunction "1_1") (pintype "passive"))
      (node (ref "A3") (pin "1") (pinfunction "1_1") (pintype "passive"))
      (node (ref "A4") (pin "1") (pinfunction "1_1") (pintype "passive"))
      (node (ref "A5") (pin "1") (pinfunction "1_1") (pintype "passive"))
      (node (ref "A6") (pin "1") (pinfunction "1_1") (pintype "passive"))
      (node (ref "A7") (pin "1") (pinfunction "1_1") (pintype "passive"))
      (node (ref "A8") (pin "1") (pinfunction "1_1") (pintype "passive"))
      (node (ref "A9") (pin "1") (pinfunction "1_1") (pintype "passive"))
      (node (ref "C1") (pin "2") (pinfunction "2_2") (pintype "passive"))
      (node (ref "C10") (pin "2") (pinfunction "2_2") (pintype "passive"))
      (node (ref "C11") (pin "2") (pinfunction "2_2") (pintype "passive"))
      (node (ref "C12") (pin "2") (pinfunction "2_2") (pintype "passive"))
      (node (ref "C13") (pin "2") (pinfunction "2_2") (pintype "passive"))
      (node (ref "C14") (pin "2") (pinfunction "2_2") (pintype "passive"))
      (node (ref "C16") (pin "2") (pinfunction "2_2") (pintype "passive"))
      (node (ref "C17") (pin "2") (pinfunction "2_2") (pintype "passive"))
      (node (ref "C18") (pin "2") (pinfunction "2_2") (pintype "passive"))
      (node (ref "C19") (pin "2") (pinfunction "2_2") (pintype "passive"))
      (node (ref "C2") (pin "2") (pinfunction "2_2") (pintype "passive"))
      (node (ref "C20") (pin "2") (pinfunction "2_2") (pintype "passive"))
      (node (ref "C21") (pin "2") (pinfunction "2_2") (pintype "passive"))
      (node (ref "C22") (pin "2") (pinfunction "2_2") (pintype "passive"))
      (node (ref "C23") (pin "2") (pinfunction "2_2") (pintype "passive"))
      (node (ref "C24") (pin "2") (pinfunction "2_2") (pintype "passive"))
      (node (ref "C25") (pin "2") (pinfunction "2_2") (pintype "passive"))
      (node (ref "C3") (pin "2") (pinfunction "2_2") (pintype "passive"))
      (node (ref "C4") (pin "2") (pinfunction "2_2") (pintype "passive"))
      (node (ref "C6") (pin "2") (pinfunction "2_2") (pintype "passive"))
      (node (ref "C7") (pin "2") (pinfunction "2_2") (pintype "passive"))
      (node (ref "C9") (pin "2") (pinfunction "2_2") (pintype "passive"))
      (node (ref "D1") (pin "2") (pinfunction "2_2") (pintype "passive"))
      (node (ref "D2") (pin "2") (pinfunction "2_2") (pintype "passive"))
      (node (ref "D3") (pin "1") (pinfunction "1_1") (pintype "passive"))
      (node (ref "D4") (pin "1") (pinfunction "1_1") (pintype "passive"))
      (node (ref "J1") (pin "5") (pinfunction "5_5") (pintype "passive"))
      (node (ref "JP1") (pin "11") (pinfunction "11_11") (pintype "passive"))
      (node (ref "JP1") (pin "14") (pinfunction "14_14") (pintype "passive"))
      (node (ref "JP1") (pin "7") (pinfunction "7_7") (pintype "passive"))
      (node (ref "JP2") (pin "7") (pinfunction "7_7") (pintype "passive"))
      (node (ref "JP3") (pin "7") (pinfunction "7_7") (pintype "passive"))
      (node (ref "JP4") (pin "7") (pinfunction "7_7") (pintype "passive"))
      (node (ref "JP5") (pin "7") (pinfunction "7_7") (pintype "passive"))
      (node (ref "JP9") (pin "2") (pinfunction "2_2") (pintype "passive"))
      (node (ref "JZ1") (pin "1") (pinfunction "1_1") (pintype "passive"))
      (node (ref "JZ2") (pin "2") (pinfunction "2_2") (pintype "passive"))
      (node (ref "JZ2") (pin "3") (pinfunction "3_3") (pintype "passive"))
      (node (ref "JZ2") (pin "4") (pinfunction "4_4") (pintype "passive"))
      (node (ref "LED1") (pin "2") (pinfunction "C_2") (pintype "passive"))
      (node (ref "P1") (pin "2") (pinfunction "Y_2") (pintype "passive"))
      (node (ref "P2") (pin "2") (pinfunction "Y_2") (pintype "passive"))
      (node (ref "P5") (pin "2") (pinfunction "2_2") (pintype "passive"))
      (node (ref "P6") (pin "2") (pinfunction "2_2") (pintype "passive"))
      (node (ref "R10") (pin "2") (pinfunction "2_2") (pintype "passive"))
      (node (ref "R13") (pin "2") (pinfunction "2_2") (pintype "passive"))
      (node (ref "R16") (pin "2") (pinfunction "2_2") (pintype "passive"))
      (node (ref "R17") (pin "2") (pinfunction "2_2") (pintype "passive"))
      (node (ref "R3") (pin "2") (pinfunction "2_2") (pintype "passive"))
      (node (ref "R4") (pin "2") (pinfunction "2_2") (pintype "passive"))
      (node (ref "R6") (pin "2") (pinfunction "2_2") (pintype "passive"))
      (node (ref "R7") (pin "2") (pinfunction "2_2") (pintype "passive"))
      (node (ref "R9") (pin "2") (pinfunction "2_2") (pintype "passive"))
      (node (ref "T1") (pin "5") (pinfunction "5_5") (pintype "passive"))
      (node (ref "T2") (pin "5") (pinfunction "5_5") (pintype "passive"))
      (node (ref "T3") (pin "2") (pinfunction "2_2") (pintype "passive"))
      (node (ref "U1") (pin "17") (pinfunction "VSS_17") (pintype "passive"))
      (node (ref "U1") (pin "6") (pinfunction "AVSS_6") (pintype "passive"))
      (node (ref "U2") (pin "3") (pinfunction "GND_3") (pintype "passive"))
      (node (ref "U3") (pin "3") (pinfunction "GND_3") (pintype "passive"))
      (node (ref "U4") (pin "1") (pinfunction "1_1") (pintype "passive"))
      (node (ref "U5") (pin "1") (pinfunction "GND_1") (pintype "passive"))
      (node (ref "U5") (pin "10") (pinfunction "GND_10") (pintype "passive"))
      (node (ref "U5") (pin "11") (pinfunction "GND_11") (pintype "passive"))
      (node (ref "U5") (pin "12") (pinfunction "GND_12") (pintype "passive"))
      (node (ref "U5") (pin "14") (pinfunction "GND_14") (pintype "passive"))
      (node (ref "U5") (pin "15") (pinfunction "GND_15") (pintype "passive"))
      (node (ref "U5") (pin "18") (pinfunction "GND_18") (pintype "passive"))
      (node (ref "U5") (pin "19") (pinfunction "GND_19") (pintype "passive"))
      (node (ref "U5") (pin "2") (pinfunction "GND_2") (pintype "passive"))
      (node (ref "U5") (pin "4") (pinfunction "GND_4") (pintype "passive"))
      (node (ref "U5") (pin "5") (pinfunction "GND_5") (pintype "passive"))
      (node (ref "U5") (pin "6") (pinfunction "GND_6") (pintype "passive"))
      (node (ref "U5") (pin "7") (pinfunction "GND_7") (pintype "passive"))
      (node (ref "U5") (pin "9") (pinfunction "GND_9") (pintype "passive"))
      (node (ref "U6") (pin "1") (pinfunction "GND_1") (pintype "passive"))
    )
    (net (code "49") (name "Net-(C2-Pad1)") (class "Default")
      (node (ref "C2") (pin "1") (pinfunction "1_1") (pintype "passive"))
      (node (ref "J1") (pin "1") (pinfunction "1_1") (pintype "passive"))
      (node (ref "R1") (pin "1") (pinfunction "1_1") (pintype "passive"))
    )
    (net (code "50") (name "Net-(C6-Pad1)") (class "Default")
      (node (ref "C6") (pin "1") (pinfunction "1_1") (pintype "passive"))
      (node (ref "T3") (pin "5") (pinfunction "5_5") (pintype "passive"))
      (node (ref "T3") (pin "6") (pinfunction "6_6") (pintype "passive"))
    )
    (net (code "51") (name "Net-(C8-Pad1)") (class "Default")
      (node (ref "C8") (pin "1") (pinfunction "1_1") (pintype "passive"))
      (node (ref "T2") (pin "2") (pinfunction "2_2") (pintype "passive"))
    )
    (net (code "52") (name "Net-(C10-Pad1)") (class "Default")
      (node (ref "C10") (pin "1") (pinfunction "1_1") (pintype "passive"))
      (node (ref "C11") (pin "1") (pinfunction "1_1") (pintype "passive"))
      (node (ref "L1") (pin "2") (pinfunction "2_2") (pintype "passive"))
      (node (ref "L2") (pin "1") (pinfunction "1_1") (pintype "passive"))
    )
    (net (code "53") (name "Net-(C12-Pad1)") (class "Default")
      (node (ref "C12") (pin "1") (pinfunction "1_1") (pintype "passive"))
      (node (ref "C14") (pin "1") (pinfunction "1_1") (pintype "passive"))
      (node (ref "L2") (pin "2") (pinfunction "2_2") (pintype "passive"))
      (node (ref "L3") (pin "1") (pinfunction "1_1") (pintype "passive"))
    )
    (net (code "54") (name "Net-(C13-Pad1)") (class "Default")
      (node (ref "C13") (pin "1") (pinfunction "1_1") (pintype "passive"))
      (node (ref "L3") (pin "2") (pinfunction "2_2") (pintype "passive"))
      (node (ref "T1") (pin "1") (pinfunction "1_1") (pintype "passive"))
    )
    (net (code "55") (name "Net-(C16-Pad1)") (class "Default")
      (node (ref "C16") (pin "1") (pinfunction "1_1") (pintype "passive"))
      (node (ref "R11") (pin "2") (pinfunction "2_2") (pintype "passive"))
      (node (ref "R12") (pin "1") (pinfunction "1_1") (pintype "passive"))
    )
    (net (code "56") (name "Net-(D5-K)") (class "Default")
      (node (ref "D5") (pin "2") (pinfunction "K_2") (pintype "passive"))
      (node (ref "R11") (pin "1") (pinfunction "1_1") (pintype "passive"))
    )
    (net (code "57") (name "Net-(JP6-Pad1)") (class "Default")
      (node (ref "JP6") (pin "1") (pinfunction "1_1") (pintype "passive"))
      (node (ref "R24") (pin "1") (pinfunction "1_1") (pintype "passive"))
    )
    (net (code "58") (name "Net-(JP7-Pad1)") (class "Default")
      (node (ref "JP7") (pin "1") (pinfunction "1_1") (pintype "passive"))
      (node (ref "R25") (pin "1") (pinfunction "1_1") (pintype "passive"))
    )
    (net (code "59") (name "Net-(JP8-Pad1)") (class "Default")
      (node (ref "JP8") (pin "1") (pinfunction "1_1") (pintype "passive"))
      (node (ref "R26") (pin "1") (pinfunction "1_1") (pintype "passive"))
    )
    (net (code "60") (name "Net-(LED1-A)") (class "Default")
      (node (ref "LED1") (pin "1") (pinfunction "A_1") (pintype "passive"))
      (node (ref "R23") (pin "2") (pinfunction "2_2") (pintype "passive"))
    )
    (net (code "61") (name "Net-(P1-X)") (class "Default")
      (node (ref "C9") (pin "1") (pinfunction "1_1") (pintype "passive"))
      (node (ref "L1") (pin "1") (pinfunction "1_1") (pintype "passive"))
      (node (ref "P1") (pin "1") (pinfunction "X_1") (pintype "passive"))
    )
    (net (code "62") (name "Net-(P2-X)") (class "Default")
      (node (ref "P2") (pin "1") (pinfunction "X_1") (pintype "passive"))
      (node (ref "T2") (pin "1") (pinfunction "1_1") (pintype "passive"))
    )
    (net (code "63") (name "Net-(P6-Pad1)") (class "Default")
      (node (ref "P6") (pin "1") (pinfunction "1_1") (pintype "passive"))
      (node (ref "R8") (pin "2") (pinfunction "2_2") (pintype "passive"))
      (node (ref "R9") (pin "1") (pinfunction "1_1") (pintype "passive"))
    )
    (net (code "64") (name "Net-(R3-Pad1)") (class "Default")
      (node (ref "R3") (pin "1") (pinfunction "1_1") (pintype "passive"))
      (node (ref "T1") (pin "3") (pinfunction "3_3") (pintype "passive"))
    )
    (net (code "65") (name "Net-(R4-Pad1)") (class "Default")
      (node (ref "R4") (pin "1") (pinfunction "1_1") (pintype "passive"))
      (node (ref "T2") (pin "3") (pinfunction "3_3") (pintype "passive"))
    )
    (net (code "66") (name "Net-(R5-Pad1)") (class "Default")
      (node (ref "R5") (pin "1") (pinfunction "1_1") (pintype "passive"))
      (node (ref "R7") (pin "1") (pinfunction "1_1") (pintype "passive"))
      (node (ref "T1") (pin "4") (pinfunction "4_4") (pintype "passive"))
    )
    (net (code "67") (name "Net-(R10-Pad1)") (class "Default")
      (node (ref "R10") (pin "1") (pinfunction "1_1") (pintype "passive"))
      (node (ref "R8") (pin "1") (pinfunction "1_1") (pintype "passive"))
      (node (ref "T2") (pin "4") (pinfunction "4_4") (pintype "passive"))
    )
    (net (code "68") (name "Net-(T3-IN)") (class "Default")
      (node (ref "T1") (pin "2") (pinfunction "2_2") (pintype "passive"))
      (node (ref "T3") (pin "1") (pinfunction "IN_1") (pintype "passive"))
    )
    (net (code "69") (name "Net-(U1-LDO_C{slash}AP)") (class "Default")
      (node (ref "C1") (pin "1") (pinfunction "1_1") (pintype "passive"))
      (node (ref "U1") (pin "18") (pinfunction "LDO_C/AP_18") (pintype "passive"))
    )
    (net (code "70") (name "Net-(U5-RF1)") (class "Default")
      (node (ref "C5") (pin "2") (pinfunction "2_2") (pintype "passive"))
      (node (ref "U5") (pin "3") (pinfunction "RF1_3") (pintype "passive"))
    )
    (net (code "71") (name "Net-(U5-RF2)") (class "Default")
      (node (ref "C15") (pin "2") (pinfunction "2_2") (pintype "passive"))
      (node (ref "U5") (pin "13") (pinfunction "RF2_13") (pintype "passive"))
    )
    (net (code "72") (name "Net-(U5-RFC)") (class "Default")
      (node (ref "C8") (pin "2") (pinfunction "2_2") (pintype "passive"))
      (node (ref "U5") (pin "8") (pinfunction "RFC_8") (pintype "passive"))
    )
    (net (code "73") (name "Net-(U5-VDD)") (class "Default")
      (node (ref "C7") (pin "1") (pinfunction "1_1") (pintype "passive"))
      (node (ref "RB1") (pin "1") (pinfunction "1_1") (pintype "passive"))
      (node (ref "U5") (pin "20") (pinfunction "VDD_20") (pintype "passive"))
    )
    (net (code "74") (name "unconnected-(D1-Pad3)") (class "Default")
      (node (ref "D1") (pin "3") (pinfunction "3_3") (pintype "passive"))
    )
    (net (code "75") (name "unconnected-(D2-Pad3)") (class "Default")
      (node (ref "D2") (pin "3") (pinfunction "3_3") (pintype "passive"))
    )
    (net (code "76") (name "unconnected-(D3-Pad3)") (class "Default")
      (node (ref "D3") (pin "3") (pinfunction "3_3") (pintype "passive"))
    )
    (net (code "77") (name "unconnected-(D4-Pad3)") (class "Default")
      (node (ref "D4") (pin "3") (pinfunction "3_3") (pintype "passive"))
    )
    (net (code "78") (name "unconnected-(JP1-Pad4)") (class "Default")
      (node (ref "JP1") (pin "4") (pinfunction "4_4") (pintype "passive"))
    )
    (net (code "79") (name "unconnected-(JP1-Pad6)") (class "Default")
      (node (ref "JP1") (pin "6") (pinfunction "6_6") (pintype "passive"))
    )
    (net (code "80") (name "unconnected-(JP1-Pad8)") (class "Default")
      (node (ref "JP1") (pin "8") (pinfunction "8_8") (pintype "passive"))
    )
    (net (code "81") (name "unconnected-(JP1-Pad10)") (class "Default")
      (node (ref "JP1") (pin "10") (pinfunction "10_10") (pintype "passive"))
    )
    (net (code "82") (name "unconnected-(JP1-Pad12)") (class "Default")
      (node (ref "JP1") (pin "12") (pinfunction "12_12") (pintype "passive"))
    )
    (net (code "83") (name "unconnected-(JP2-Pad2)") (class "Default")
      (node (ref "JP2") (pin "2") (pinfunction "2_2") (pintype "passive"))
    )
    (net (code "84") (name "unconnected-(JP2-Pad4)") (class "Default")
      (node (ref "JP2") (pin "4") (pinfunction "4_4") (pintype "passive"))
    )
    (net (code "85") (name "unconnected-(JP3-Pad2)") (class "Default")
      (node (ref "JP3") (pin "2") (pinfunction "2_2") (pintype "passive"))
    )
    (net (code "86") (name "unconnected-(JP3-Pad4)") (class "Default")
      (node (ref "JP3") (pin "4") (pinfunction "4_4") (pintype "passive"))
    )
    (net (code "87") (name "unconnected-(M1-Pad1)") (class "Default")
      (node (ref "M1") (pin "1") (pinfunction "1_1") (pintype "passive"))
    )
    (net (code "88") (name "unconnected-(M2-Pad1)") (class "Default")
      (node (ref "M2") (pin "1") (pinfunction "1_1") (pintype "passive"))
    )
    (net (code "89") (name "unconnected-(U1-P0.7{slash}SPISCLK_1{slash}AD7-Pad32)") (class "Default")
      (node (ref "U1") (pin "32") (pinfunction "P0.7/SPISCLK_1/AD7_32") (pintype "passive"))
    )
    (net (code "90") (name "unconnected-(U1-P2.0{slash}PWM0{slash}AD8-Pad19)") (class "Default")
      (node (ref "U1") (pin "19") (pinfunction "P2.0/PWM0/AD8_19") (pintype "passive"))
    )
    (net (code "91") (name "unconnected-(U1-P2.1{slash}PWM1{slash}AD9-Pad20)") (class "Default")
      (node (ref "U1") (pin "20") (pinfunction "P2.1/PWM1/AD9_20") (pintype "passive"))
    )
    (net (code "92") (name "unconnected-(U1-P2.5{slash}PWM5{slash}AD13-Pad25)") (class "Default")
      (node (ref "U1") (pin "25") (pinfunction "P2.5/PWM5/AD13_25") (pintype "passive"))
    )
    (net (code "93") (name "unconnected-(U1-P2.6{slash}PWM6{slash}AD14-Pad26)") (class "Default")
      (node (ref "U1") (pin "26") (pinfunction "P2.6/PWM6/AD14_26") (pintype "passive"))
    )
    (net (code "94") (name "unconnected-(U1-P2.7{slash}PWM7{slash}AD15-Pad27)") (class "Default")
      (node (ref "U1") (pin "27") (pinfunction "P2.7/PWM7/AD15_27") (pintype "passive"))
    )
    (net (code "95") (name "unconnected-(U1-P3.2{slash}~{INT0}{slash}STADC-Pad8)") (class "Default")
      (node (ref "U1") (pin "8") (pinfunction "P3.2/~{INT0}/STADC_8") (pintype "passive"))
    )
    (net (code "96") (name "unconnected-(U1-P3.7{slash}~{RD}-Pad14)") (class "Default")
      (node (ref "U1") (pin "14") (pinfunction "P3.7/~{RD}_14") (pintype "passive"))
    )
    (net (code "97") (name "unconnected-(U1-P4.4{slash}~{CS}-Pad28)") (class "Default")
      (node (ref "U1") (pin "28") (pinfunction "P4.4/~{CS}_28") (pintype "passive"))
    )
    (net (code "98") (name "unconnected-(U1-P4.5{slash}ALE-Pad29)") (class "Default")
      (node (ref "U1") (pin "29") (pinfunction "P4.5/ALE_29") (pintype "passive"))
    )
    (net (code "99") (name "unconnected-(U1-XTAL1-Pad16)") (class "Default")
      (node (ref "U1") (pin "16") (pinfunction "XTAL1_16") (pintype "passive"))
    )
    (net (code "100") (name "unconnected-(U1-XTAL2-Pad15)") (class "Default")
      (node (ref "U1") (pin "15") (pinfunction "XTAL2_15") (pintype "passive"))
    )
  )
)
